# v3SchemaSimonComplet.net
KiCad netlist of a schematic drawn in EAGLE
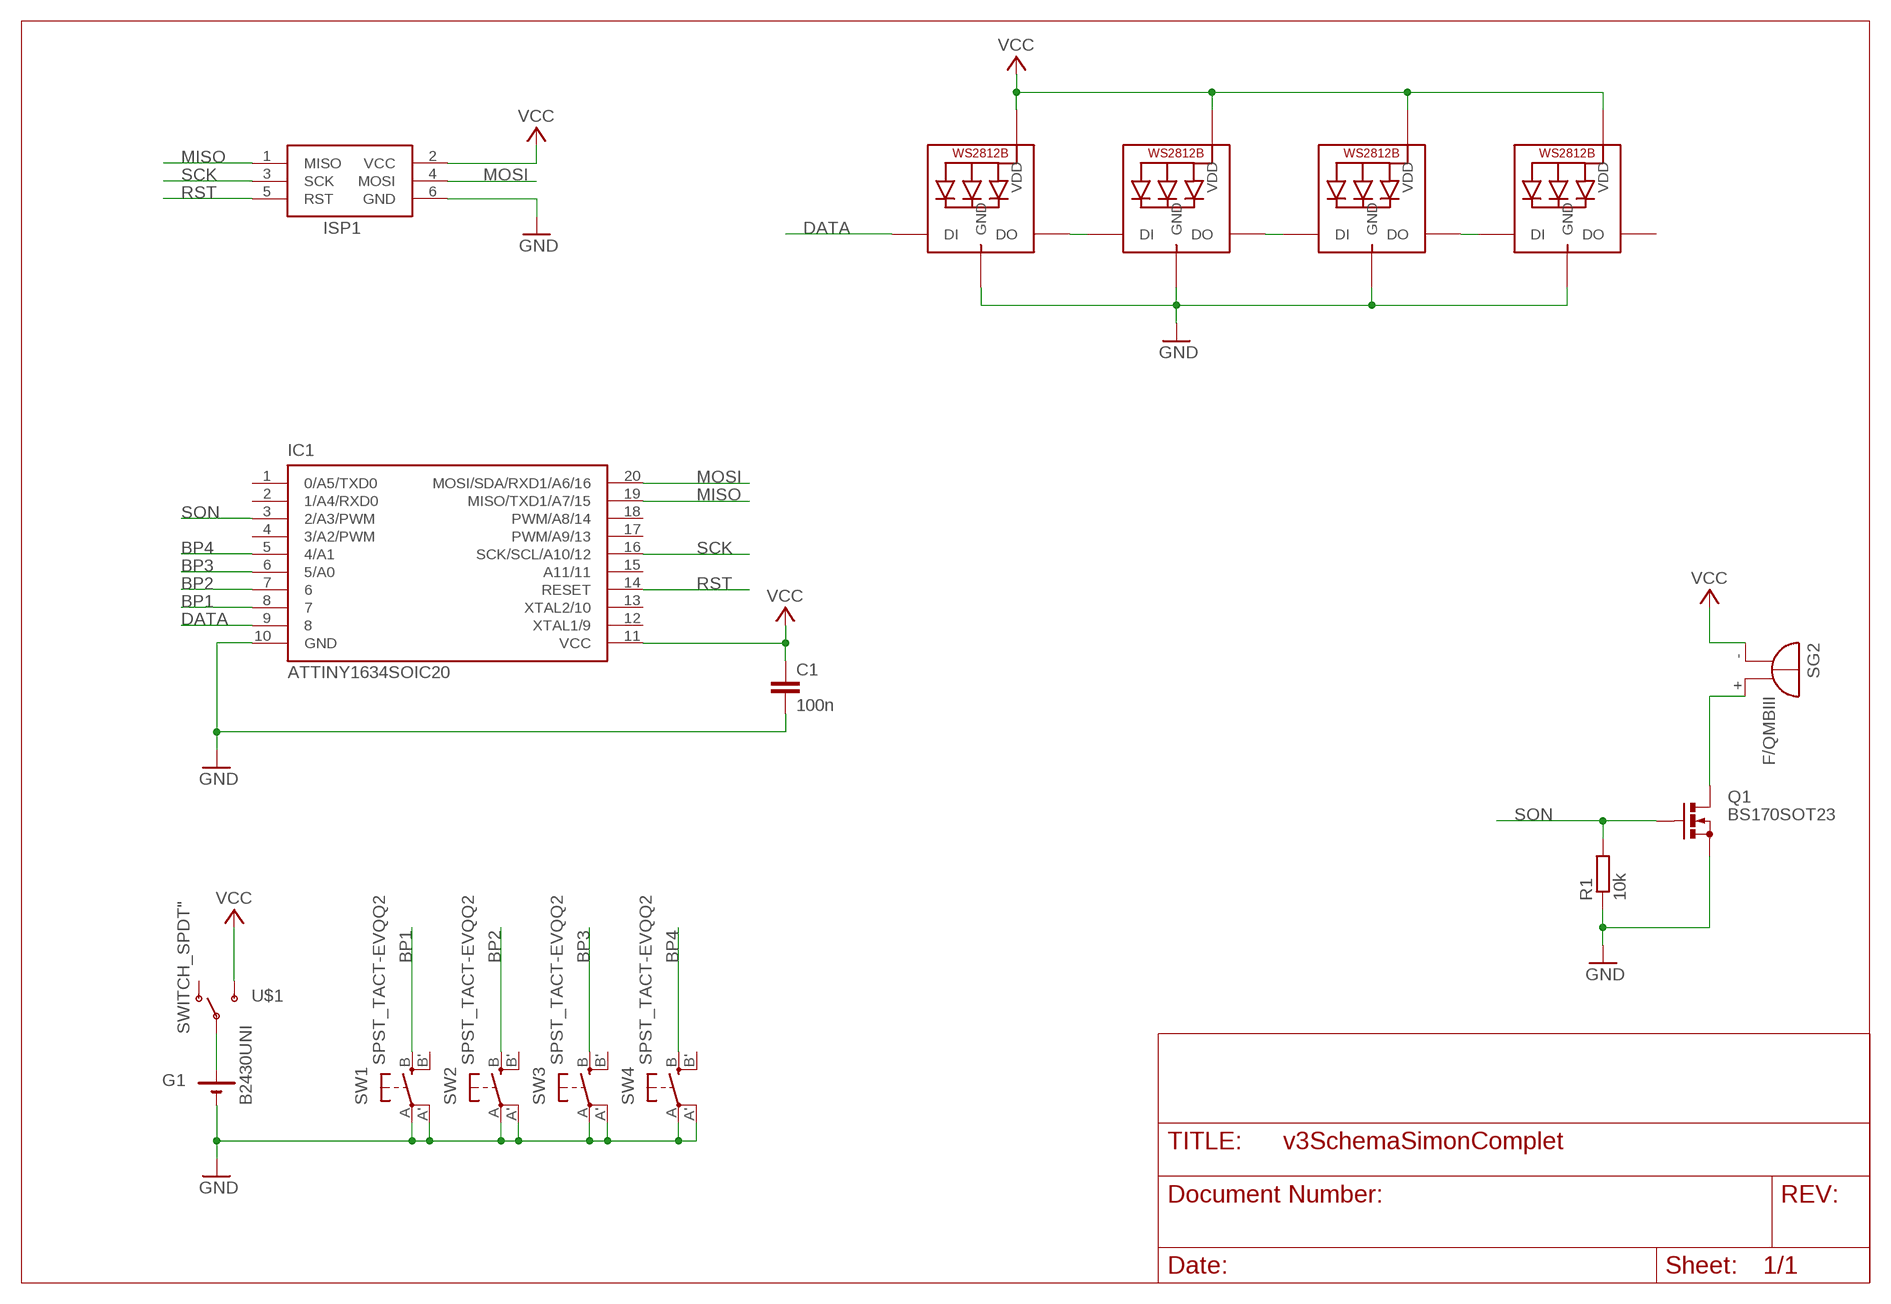
[diagram p0: schematic, sheet 1]

(export (version "E")
  (design (tool "Eeschema 10.0.6"))
  (components
    (comp (ref "C1")
      (value "100n")
      (footprint "eagle-import:C1206")
      (libsource (lib "eagle-import") (part "C-EUC1206"))
    )
    (comp (ref "G1")
      (value "B2430UNI")
      (footprint "eagle-import:B2430UNI")
      (libsource (lib "eagle-import") (part "B2430UNI"))
    )
    (comp (ref "IC1")
      (value "ATTINY1634SOIC20")
      (footprint "eagle-import:SOIC20")
      (libsource (lib "eagle-import") (part "ATTINY1634SOIC20"))
    )
    (comp (ref "ISP1")
      (value "AVRISP-6")
      (footprint "eagle-import:AVRISP")
      (libsource (lib "eagle-import") (part "AVRISP-6"))
    )
    (comp (ref "LED1")
      (value "WS2812B5050")
      (footprint "eagle-import:WS2812B")
      (libsource (lib "eagle-import") (part "WS2812B5050"))
    )
    (comp (ref "LED2")
      (value "WS2812B5050")
      (footprint "eagle-import:WS2812B")
      (libsource (lib "eagle-import") (part "WS2812B5050"))
    )
    (comp (ref "LED3")
      (value "WS2812B5050")
      (footprint "eagle-import:WS2812B")
      (libsource (lib "eagle-import") (part "WS2812B5050"))
    )
    (comp (ref "LED4")
      (value "WS2812B5050")
      (footprint "eagle-import:WS2812B")
      (libsource (lib "eagle-import") (part "WS2812B5050"))
    )
    (comp (ref "Q1")
      (value "BS170SOT23")
      (footprint "eagle-import:SOT23")
      (libsource (lib "eagle-import") (part "BS170SOT23"))
    )
    (comp (ref "R1")
      (value "10k")
      (footprint "eagle-import:R1206")
      (libsource (lib "eagle-import") (part "R-EUR1206"))
    )
    (comp (ref "SG2")
      (value "F/QMBIII")
      (footprint "eagle-import:F_QMBIII")
      (libsource (lib "eagle-import") (part "F/QMBIII"))
    )
    (comp (ref "SW1")
      (value "SPST_TACT-EVQQ2")
      (footprint "eagle-import:EVQ-Q2")
      (libsource (lib "eagle-import") (part "SPST_TACT-EVQQ2"))
    )
    (comp (ref "SW2")
      (value "SPST_TACT-EVQQ2")
      (footprint "eagle-import:EVQ-Q2")
      (libsource (lib "eagle-import") (part "SPST_TACT-EVQQ2"))
    )
    (comp (ref "SW3")
      (value "SPST_TACT-EVQQ2")
      (footprint "eagle-import:EVQ-Q2")
      (libsource (lib "eagle-import") (part "SPST_TACT-EVQQ2"))
    )
    (comp (ref "SW4")
      (value "SPST_TACT-EVQQ2")
      (footprint "eagle-import:EVQ-Q2")
      (libsource (lib "eagle-import") (part "SPST_TACT-EVQQ2"))
    )
    (comp (ref "U$1")
      (value "SWITCH_SPDT\"")
      (footprint "eagle-import:CMS-CL-SB-12A-02T")
      (libsource (lib "eagle-import") (part "SWITCH_SPDT{dblquote}"))
    )
  )
  (nets
    (net (code "1") (name "/BP1") (class "Default")
      (node (ref "IC1") (pin "8") (pinfunction "7_8") (pintype "bidirectional"))
      (node (ref "SW1") (pin "B") (pinfunction "S_B") (pintype "passive"))
    )
    (net (code "2") (name "/BP2") (class "Default")
      (node (ref "IC1") (pin "7") (pinfunction "6_7") (pintype "bidirectional"))
      (node (ref "SW2") (pin "B") (pinfunction "S_B") (pintype "passive"))
    )
    (net (code "3") (name "/BP3") (class "Default")
      (node (ref "IC1") (pin "6") (pinfunction "5/A0_6") (pintype "bidirectional"))
      (node (ref "SW3") (pin "B") (pinfunction "S_B") (pintype "passive"))
    )
    (net (code "4") (name "/BP4") (class "Default")
      (node (ref "IC1") (pin "5") (pinfunction "4/A1_5") (pintype "bidirectional"))
      (node (ref "SW4") (pin "B") (pinfunction "S_B") (pintype "passive"))
    )
    (net (code "5") (name "/DATA") (class "Default")
      (node (ref "IC1") (pin "9") (pinfunction "8_9") (pintype "bidirectional"))
      (node (ref "LED1") (pin "4-DIN") (pinfunction "DI_4-DIN") (pintype "input"))
    )
    (net (code "6") (name "/MISO") (class "Default")
      (node (ref "IC1") (pin "19") (pinfunction "MISO/TXD1/A7/15_19") (pintype "bidirectional"))
      (node (ref "ISP1") (pin "1") (pinfunction "MISO_1") (pintype "input"))
    )
    (net (code "7") (name "/MOSI") (class "Default")
      (node (ref "IC1") (pin "20") (pinfunction "MOSI/SDA/RXD1/A6/16_20") (pintype "bidirectional"))
      (node (ref "ISP1") (pin "4") (pinfunction "MOSI_4") (pintype "output"))
    )
    (net (code "8") (name "/RST") (class "Default")
      (node (ref "IC1") (pin "14") (pinfunction "RESET_14") (pintype "bidirectional"))
      (node (ref "ISP1") (pin "5") (pinfunction "RST_5") (pintype "output"))
    )
    (net (code "9") (name "/SCK") (class "Default")
      (node (ref "IC1") (pin "16") (pinfunction "SCK/SCL/A10/12_16") (pintype "bidirectional"))
      (node (ref "ISP1") (pin "3") (pinfunction "SCK_3") (pintype "output"))
    )
    (net (code "10") (name "/SON") (class "Default")
      (node (ref "IC1") (pin "3") (pinfunction "2/A3/PWM_3") (pintype "bidirectional"))
      (node (ref "Q1") (pin "1") (pinfunction "G_1") (pintype "passive"))
      (node (ref "R1") (pin "2") (pinfunction "2_2") (pintype "passive"))
    )
    (net (code "11") (name "GND") (class "Default")
      (node (ref "C1") (pin "2") (pinfunction "2_2") (pintype "passive"))
      (node (ref "G1") (pin "-@1") (pinfunction "-_-@1") (pintype "passive"))
      (node (ref "IC1") (pin "10") (pinfunction "GND_10") (pintype "power_in"))
      (node (ref "ISP1") (pin "6") (pinfunction "GND_6") (pintype "power_in"))
      (node (ref "LED1") (pin "3-GND") (pinfunction "GND_3-GND") (pintype "power_in"))
      (node (ref "LED2") (pin "3-GND") (pinfunction "GND_3-GND") (pintype "power_in"))
      (node (ref "LED3") (pin "3-GND") (pinfunction "GND_3-GND") (pintype "power_in"))
      (node (ref "LED4") (pin "3-GND") (pinfunction "GND_3-GND") (pintype "power_in"))
      (node (ref "Q1") (pin "2") (pinfunction "S_2") (pintype "passive"))
      (node (ref "R1") (pin "1") (pinfunction "1_1") (pintype "passive"))
      (node (ref "SW1") (pin "A") (pinfunction "P_A") (pintype "passive"))
      (node (ref "SW1") (pin "A'") (pinfunction "P1_A'") (pintype "passive"))
      (node (ref "SW2") (pin "A") (pinfunction "P_A") (pintype "passive"))
      (node (ref "SW2") (pin "A'") (pinfunction "P1_A'") (pintype "passive"))
      (node (ref "SW3") (pin "A") (pinfunction "P_A") (pintype "passive"))
      (node (ref "SW3") (pin "A'") (pinfunction "P1_A'") (pintype "passive"))
      (node (ref "SW4") (pin "A") (pinfunction "P_A") (pintype "passive"))
      (node (ref "SW4") (pin "A'") (pinfunction "P1_A'") (pintype "passive"))
    )
    (net (code "12") (name "Net-(G1-+)") (class "Default")
      (node (ref "G1") (pin "+@1") (pinfunction "+_+@1") (pintype "passive"))
      (node (ref "U$1") (pin "2") (pinfunction "P_2") (pintype "passive"))
    )
    (net (code "13") (name "Net-(LED1-DO)") (class "Default")
      (node (ref "LED1") (pin "2-DOUT") (pinfunction "DO_2-DOUT") (pintype "output"))
      (node (ref "LED2") (pin "4-DIN") (pinfunction "DI_4-DIN") (pintype "input"))
    )
    (net (code "14") (name "Net-(LED2-DO)") (class "Default")
      (node (ref "LED2") (pin "2-DOUT") (pinfunction "DO_2-DOUT") (pintype "output"))
      (node (ref "LED3") (pin "4-DIN") (pinfunction "DI_4-DIN") (pintype "input"))
    )
    (net (code "15") (name "Net-(LED3-DO)") (class "Default")
      (node (ref "LED3") (pin "2-DOUT") (pinfunction "DO_2-DOUT") (pintype "output"))
      (node (ref "LED4") (pin "4-DIN") (pinfunction "DI_4-DIN") (pintype "input"))
    )
    (net (code "16") (name "Net-(Q1-D)") (class "Default")
      (node (ref "Q1") (pin "3") (pinfunction "D_3") (pintype "passive"))
      (node (ref "SG2") (pin "+") (pinfunction "-_+") (pintype "passive"))
    )
    (net (code "17") (name "VCC") (class "Default")
      (node (ref "C1") (pin "1") (pinfunction "1_1") (pintype "passive"))
      (node (ref "IC1") (pin "11") (pinfunction "VCC_11") (pintype "power_in"))
      (node (ref "ISP1") (pin "2") (pinfunction "VCC_2") (pintype "power_in"))
      (node (ref "LED1") (pin "1-VDD") (pinfunction "VDD_1-VDD") (pintype "power_in"))
      (node (ref "LED2") (pin "1-VDD") (pinfunction "VDD_1-VDD") (pintype "power_in"))
      (node (ref "LED3") (pin "1-VDD") (pinfunction "VDD_1-VDD") (pintype "power_in"))
      (node (ref "LED4") (pin "1-VDD") (pinfunction "VDD_1-VDD") (pintype "power_in"))
      (node (ref "SG2") (pin "-") (pinfunction "+_-") (pintype "passive"))
      (node (ref "U$1") (pin "3") (pinfunction "S_3") (pintype "passive"))
    )
    (net (code "18") (name "unconnected-(IC1-0{slash}A5{slash}TXD0-Pad1)") (class "Default")
      (node (ref "IC1") (pin "1") (pinfunction "0/A5/TXD0_1") (pintype "bidirectional"))
    )
    (net (code "19") (name "unconnected-(IC1-1{slash}A4{slash}RXD0-Pad2)") (class "Default")
      (node (ref "IC1") (pin "2") (pinfunction "1/A4/RXD0_2") (pintype "bidirectional"))
    )
    (net (code "20") (name "unconnected-(IC1-3{slash}A2{slash}PWM-Pad4)") (class "Default")
      (node (ref "IC1") (pin "4") (pinfunction "3/A2/PWM_4") (pintype "bidirectional"))
    )
    (net (code "21") (name "unconnected-(IC1-A11{slash}11-Pad15)") (class "Default")
      (node (ref "IC1") (pin "15") (pinfunction "A11/11_15") (pintype "bidirectional"))
    )
    (net (code "22") (name "unconnected-(IC1-PWM{slash}A8{slash}14-Pad18)") (class "Default")
      (node (ref "IC1") (pin "18") (pinfunction "PWM/A8/14_18") (pintype "bidirectional"))
    )
    (net (code "23") (name "unconnected-(IC1-PWM{slash}A9{slash}13-Pad17)") (class "Default")
      (node (ref "IC1") (pin "17") (pinfunction "PWM/A9/13_17") (pintype "bidirectional"))
    )
    (net (code "24") (name "unconnected-(IC1-XTAL1{slash}9-Pad12)") (class "Default")
      (node (ref "IC1") (pin "12") (pinfunction "XTAL1/9_12") (pintype "bidirectional"))
    )
    (net (code "25") (name "unconnected-(IC1-XTAL2{slash}10-Pad13)") (class "Default")
      (node (ref "IC1") (pin "13") (pinfunction "XTAL2/10_13") (pintype "bidirectional"))
    )
    (net (code "26") (name "unconnected-(LED4-DO-Pad2-DOUT)") (class "Default")
      (node (ref "LED4") (pin "2-DOUT") (pinfunction "DO_2-DOUT") (pintype "output"))
    )
    (net (code "27") (name "unconnected-(SW1-S1-PadB')") (class "Default")
      (node (ref "SW1") (pin "B'") (pinfunction "S1_B'") (pintype "passive"))
    )
    (net (code "28") (name "unconnected-(SW2-S1-PadB')") (class "Default")
      (node (ref "SW2") (pin "B'") (pinfunction "S1_B'") (pintype "passive"))
    )
    (net (code "29") (name "unconnected-(SW3-S1-PadB')") (class "Default")
      (node (ref "SW3") (pin "B'") (pinfunction "S1_B'") (pintype "passive"))
    )
    (net (code "30") (name "unconnected-(SW4-S1-PadB')") (class "Default")
      (node (ref "SW4") (pin "B'") (pinfunction "S1_B'") (pintype "passive"))
    )
    (net (code "31") (name "unconnected-(U$1-O-Pad1)") (class "Default")
      (node (ref "U$1") (pin "1") (pinfunction "O_1") (pintype "passive"))
    )
  )
)
